# controlMotores.net
KiCad netlist of a schematic drawn in EAGLE
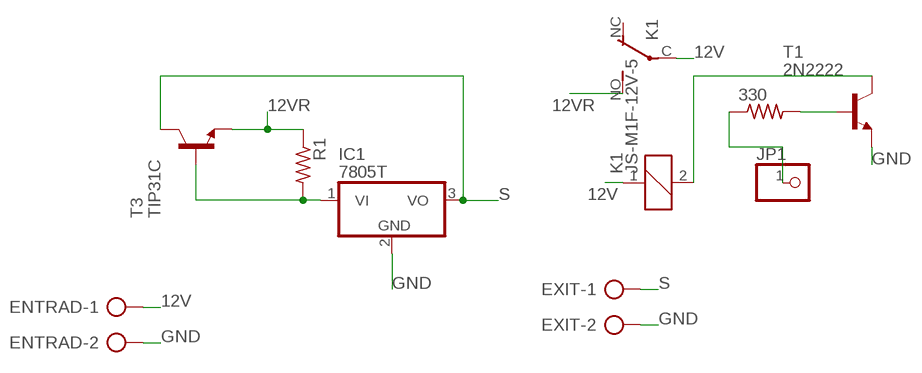
[diagram p0: schematic, sheet 1]

(export (version "E")
  (design (tool "Eeschema 10.0.6"))
  (components
    (comp (ref "330")
      (value "R-US_0204/7")
      (footprint "eagle-import:0204_7")
      (libsource (lib "eagle-import") (part "R-US_0204/7"))
    )
    (comp (ref "ENTRAD")
      (value "AK500/2-H")
      (footprint "eagle-import:AK500_2-H")
      (libsource (lib "eagle-import") (part "AK500/2-H"))
    )
    (comp (ref "EXIT")
      (value "AK500/2-H")
      (footprint "eagle-import:AK500_2-H")
      (libsource (lib "eagle-import") (part "AK500/2-H"))
    )
    (comp (ref "IC1")
      (value "7805T")
      (footprint "eagle-import:TO220H")
      (libsource (lib "eagle-import") (part "78T05"))
    )
    (comp (ref "JP1")
      (value "PINHD-1X1")
      (footprint "eagle-import:1X01")
      (libsource (lib "eagle-import") (part "PINHD-1X1"))
    )
    (comp (ref "K1")
      (value "JS-M1F-12V-5")
      (footprint "eagle-import:JS-M")
      (libsource (lib "eagle-import") (part "JS-M1F-12V-5"))
    )
    (comp (ref "R1")
      (value "R-US_0207/12")
      (footprint "eagle-import:0207_12")
      (libsource (lib "eagle-import") (part "R-US_0207/12"))
    )
    (comp (ref "T1")
      (value "2N2222")
      (footprint "eagle-import:TO18")
      (libsource (lib "eagle-import") (part "2N2222"))
    )
    (comp (ref "T3")
      (value "TIP31C")
      (footprint "eagle-import:TO220")
      (libsource (lib "eagle-import") (part "TIP31C"))
    )
  )
  (nets
    (net (code "1") (name "/12V") (class "Default")
      (node (ref "ENTRAD") (pin "1") (pinfunction "KL_1") (pintype "passive"))
      (node (ref "K1") (pin "1") (pinfunction "1_1") (pintype "passive"))
      (node (ref "K1") (pin "C") (pinfunction "P_C") (pintype "passive"))
    )
    (net (code "2") (name "/12VR") (class "Default")
      (node (ref "K1") (pin "NO") (pinfunction "S_NO") (pintype "passive"))
      (node (ref "R1") (pin "1") (pinfunction "1_1") (pintype "passive"))
      (node (ref "T3") (pin "3") (pinfunction "E_3") (pintype "passive"))
    )
    (net (code "3") (name "/GND") (class "Default")
      (node (ref "ENTRAD") (pin "2") (pinfunction "KL_2") (pintype "passive"))
      (node (ref "EXIT") (pin "2") (pinfunction "KL_2") (pintype "passive"))
      (node (ref "IC1") (pin "2") (pinfunction "GND_2") (pintype "passive"))
      (node (ref "T1") (pin "1") (pinfunction "E_1") (pintype "passive"))
    )
    (net (code "4") (name "/S") (class "Default")
      (node (ref "EXIT") (pin "1") (pinfunction "KL_1") (pintype "passive"))
      (node (ref "IC1") (pin "3") (pinfunction "VO_3") (pintype "passive"))
      (node (ref "T3") (pin "2") (pinfunction "C_2") (pintype "passive"))
    )
    (net (code "5") (name "Net-(330-Pad1)") (class "Default")
      (node (ref "330") (pin "1") (pinfunction "1_1") (pintype "passive"))
      (node (ref "JP1") (pin "1") (pinfunction "1_1") (pintype "passive"))
    )
    (net (code "6") (name "Net-(IC1-VI)") (class "Default")
      (node (ref "IC1") (pin "1") (pinfunction "VI_1") (pintype "input"))
      (node (ref "R1") (pin "2") (pinfunction "2_2") (pintype "passive"))
      (node (ref "T3") (pin "1") (pinfunction "B_1") (pintype "passive"))
    )
    (net (code "7") (name "Net-(T1-B)") (class "Default")
      (node (ref "330") (pin "2") (pinfunction "2_2") (pintype "passive"))
      (node (ref "T1") (pin "2") (pinfunction "B_2") (pintype "passive"))
    )
    (net (code "8") (name "Net-(T1-C)") (class "Default")
      (node (ref "K1") (pin "2") (pinfunction "2_2") (pintype "passive"))
      (node (ref "T1") (pin "3") (pinfunction "C_3") (pintype "passive"))
    )
    (net (code "9") (name "unconnected-(K1B-O-PadNC)") (class "Default")
      (node (ref "K1") (pin "NC") (pinfunction "O_NC") (pintype "passive"))
    )
  )
)
